# max30205.net
KiCad netlist of a schematic drawn in EAGLE
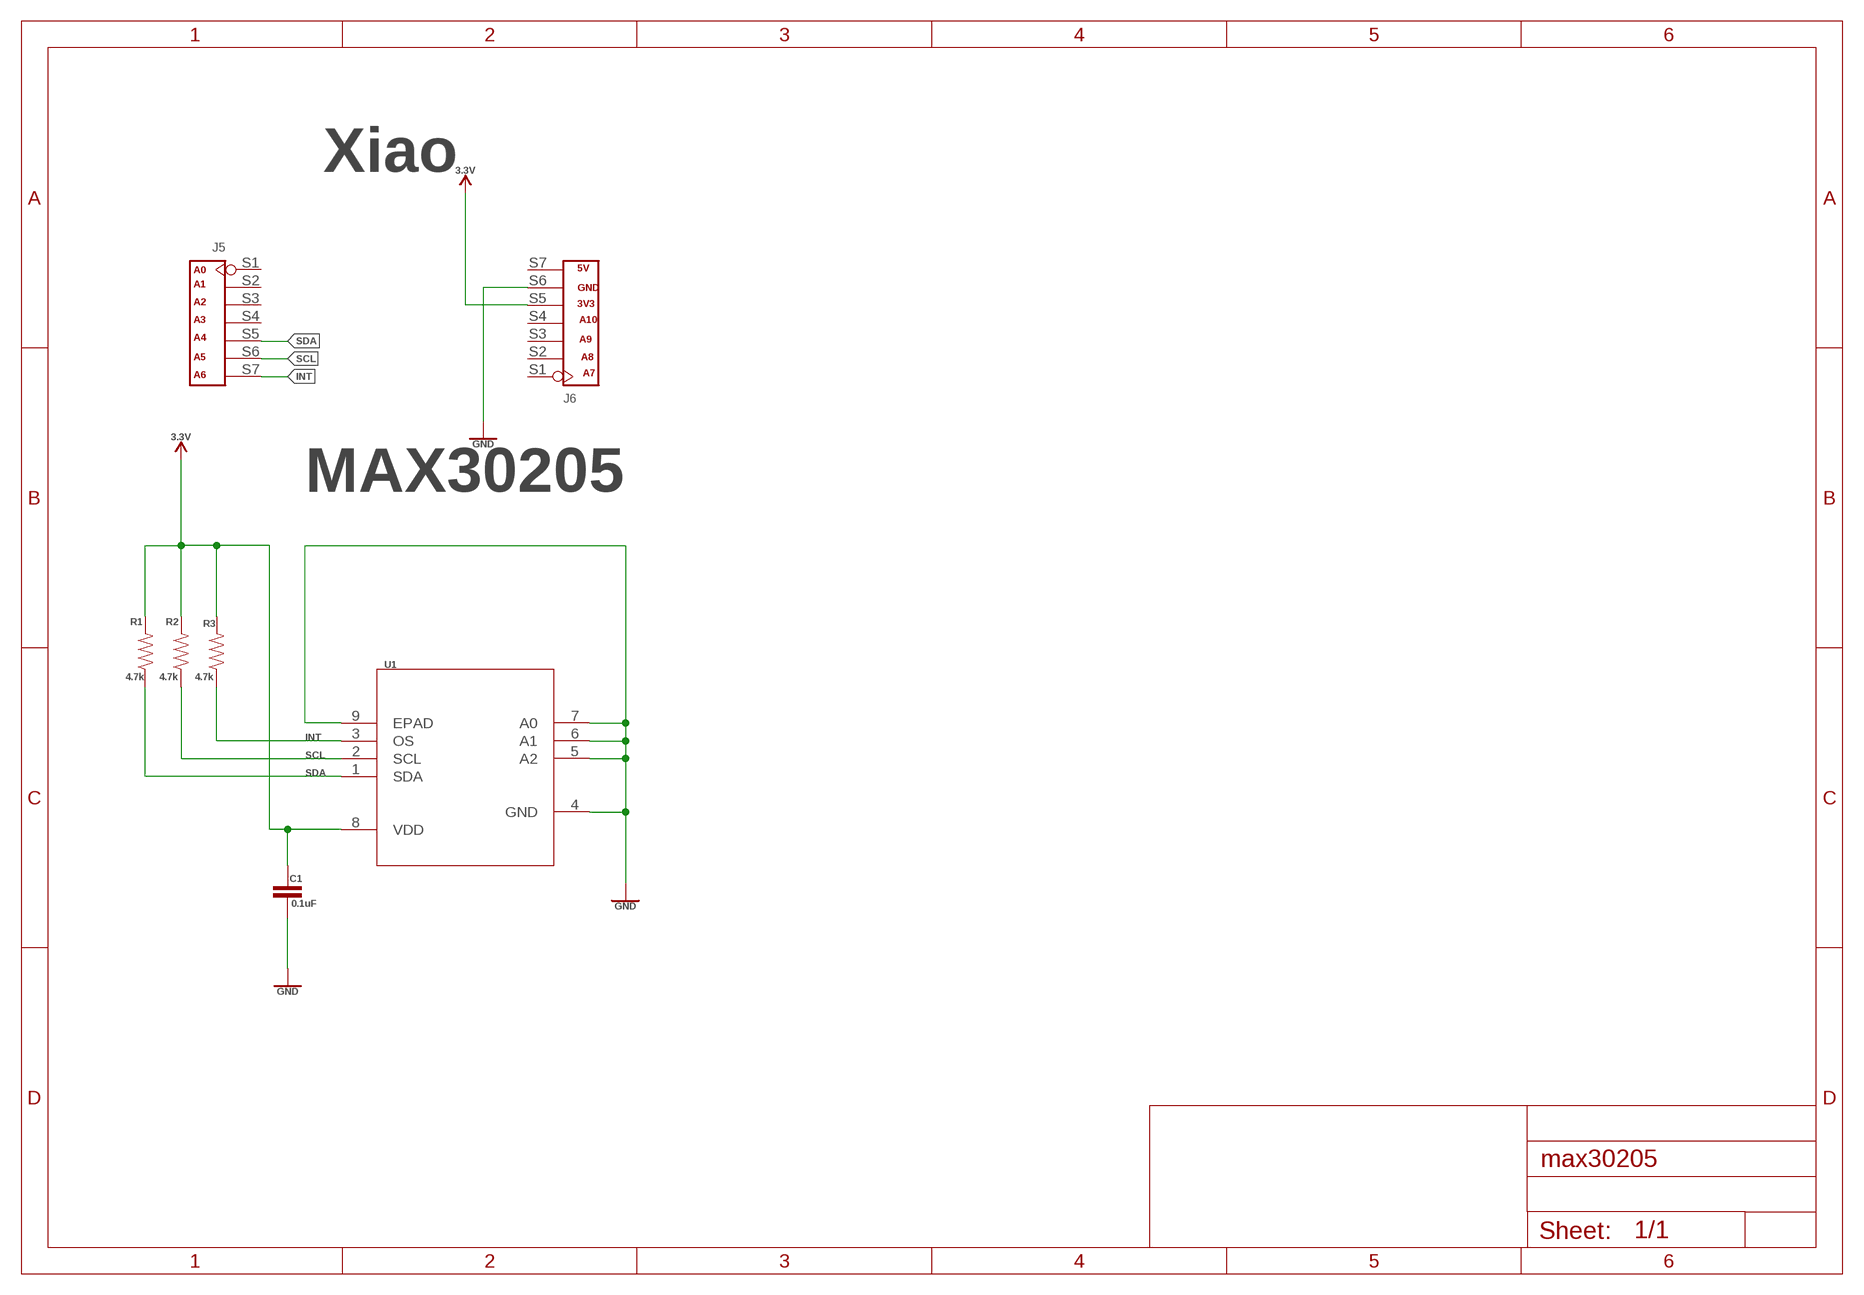
[diagram p0: schematic, sheet 1]

(export (version "E")
  (design (tool "Eeschema 10.0.6"))
  (components
    (comp (ref "C1")
      (value "0.1uF")
      (footprint "eagle-import:0603")
      (libsource (lib "eagle-import") (part "0.1UF-0603-25V-(+80/-20%)"))
    )
    (comp (ref "J5")
      (value "DNP")
      (footprint "eagle-import:CONNECTOR-V2")
      (libsource (lib "eagle-import") (part "CONNECTOR-NEW_HEADER-7P-HALF-HOLE"))
    )
    (comp (ref "J6")
      (value "DNP")
      (footprint "eagle-import:CONNECTOR-V2")
      (libsource (lib "eagle-import") (part "CONNECTOR-NEW_HEADER-7P-HALF-HOLE"))
    )
    (comp (ref "R1")
      (value "4.7k")
      (footprint "eagle-import:0603")
      (libsource (lib "eagle-import") (part "4.7KOHM-0603-1/10W-1%"))
    )
    (comp (ref "R2")
      (value "4.7k")
      (footprint "eagle-import:0603")
      (libsource (lib "eagle-import") (part "4.7KOHM-0603-1/10W-1%"))
    )
    (comp (ref "R3")
      (value "4.7k")
      (footprint "eagle-import:0603")
      (libsource (lib "eagle-import") (part "4.7KOHM-0603-1/10W-1%"))
    )
    (comp (ref "U1")
      (value "MAX30205MTA+T21-0137I_T833-2_MXM-M")
      (footprint "eagle-import:21-0137I_T833-2_MXM-M")
      (fields
        (field (name "MANUFACTURER_PART_NUMBER") "MAX30205MTA+T")
        (field (name "COPYRIGHT") "Copyright (C) 2018 Accelerated Designs. All rights reserved")
      )
      (libsource (lib "eagle-import") (part "MAX30205MTA+T21-0137I_T833-2_MXM-M"))
    )
  )
  (nets
    (net (code "1") (name "3.3V") (class "Default")
      (node (ref "C1") (pin "1") (pinfunction "1_1") (pintype "passive"))
      (node (ref "J6") (pin "S5") (pinfunction "5_S5") (pintype "bidirectional"))
      (node (ref "R1") (pin "2") (pinfunction "2_2") (pintype "passive"))
      (node (ref "R2") (pin "2") (pinfunction "2_2") (pintype "passive"))
      (node (ref "R3") (pin "2") (pinfunction "2_2") (pintype "passive"))
      (node (ref "U1") (pin "8") (pinfunction "VDD_8") (pintype "power_in"))
    )
    (net (code "2") (name "GND") (class "Default")
      (node (ref "C1") (pin "2") (pinfunction "2_2") (pintype "passive"))
      (node (ref "J6") (pin "S6") (pinfunction "6_S6") (pintype "bidirectional"))
      (node (ref "U1") (pin "4") (pinfunction "GND_4") (pintype "passive"))
      (node (ref "U1") (pin "5") (pinfunction "A2_5") (pintype "bidirectional"))
      (node (ref "U1") (pin "6") (pinfunction "A1_6") (pintype "bidirectional"))
      (node (ref "U1") (pin "7") (pinfunction "A0_7") (pintype "bidirectional"))
      (node (ref "U1") (pin "9") (pinfunction "EPAD_9") (pintype "passive"))
    )
    (net (code "3") (name "INT") (class "Default")
      (node (ref "J5") (pin "S7") (pinfunction "7_S7") (pintype "bidirectional"))
      (node (ref "R3") (pin "1") (pinfunction "1_1") (pintype "passive"))
      (node (ref "U1") (pin "3") (pinfunction "OS_3") (pintype "passive"))
    )
    (net (code "4") (name "SCL") (class "Default")
      (node (ref "J5") (pin "S6") (pinfunction "6_S6") (pintype "bidirectional"))
      (node (ref "R2") (pin "1") (pinfunction "1_1") (pintype "passive"))
      (node (ref "U1") (pin "2") (pinfunction "SCL_2") (pintype "passive"))
    )
    (net (code "5") (name "SDA") (class "Default")
      (node (ref "J5") (pin "S5") (pinfunction "5_S5") (pintype "bidirectional"))
      (node (ref "R1") (pin "1") (pinfunction "1_1") (pintype "passive"))
      (node (ref "U1") (pin "1") (pinfunction "SDA_1") (pintype "passive"))
    )
    (net (code "6") (name "unconnected-(J5-1-PadS1)") (class "Default")
      (node (ref "J5") (pin "S1") (pinfunction "1_S1") (pintype "bidirectional"))
    )
    (net (code "7") (name "unconnected-(J5-2-PadS2)") (class "Default")
      (node (ref "J5") (pin "S2") (pinfunction "2_S2") (pintype "bidirectional"))
    )
    (net (code "8") (name "unconnected-(J5-3-PadS3)") (class "Default")
      (node (ref "J5") (pin "S3") (pinfunction "3_S3") (pintype "bidirectional"))
    )
    (net (code "9") (name "unconnected-(J5-4-PadS4)") (class "Default")
      (node (ref "J5") (pin "S4") (pinfunction "4_S4") (pintype "bidirectional"))
    )
    (net (code "10") (name "unconnected-(J6-1-PadS1)") (class "Default")
      (node (ref "J6") (pin "S1") (pinfunction "1_S1") (pintype "bidirectional"))
    )
    (net (code "11") (name "unconnected-(J6-2-PadS2)") (class "Default")
      (node (ref "J6") (pin "S2") (pinfunction "2_S2") (pintype "bidirectional"))
    )
    (net (code "12") (name "unconnected-(J6-3-PadS3)") (class "Default")
      (node (ref "J6") (pin "S3") (pinfunction "3_S3") (pintype "bidirectional"))
    )
    (net (code "13") (name "unconnected-(J6-4-PadS4)") (class "Default")
      (node (ref "J6") (pin "S4") (pinfunction "4_S4") (pintype "bidirectional"))
    )
    (net (code "14") (name "unconnected-(J6-7-PadS7)") (class "Default")
      (node (ref "J6") (pin "S7") (pinfunction "7_S7") (pintype "bidirectional"))
    )
  )
)
